# football_robot_main_board.net
KiCad netlist of a schematic drawn in Altium Designer
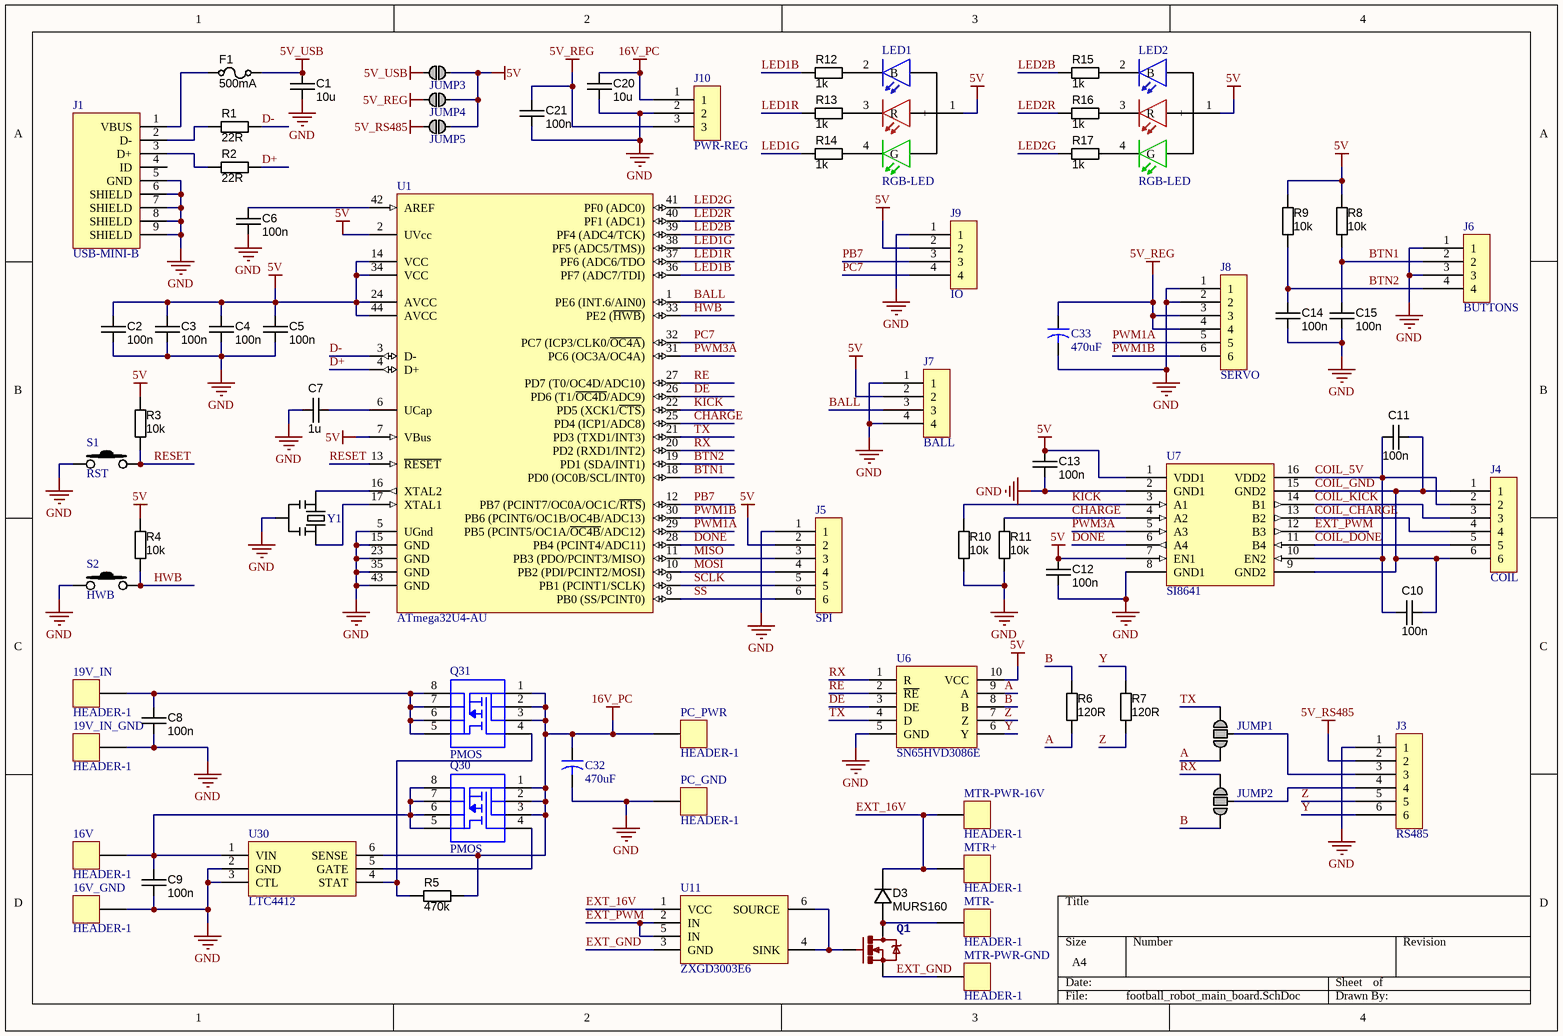
[diagram p0: football_robot_main_board.SchDoc]

(export (version "E")
  (design (tool "Eeschema 10.0.6"))
  (components
    (comp (ref "16V")
      (value "HEADER-1")
      (footprint "POWER-VIA")
      (libsource (lib "connectors") (part "HEADER-1"))
    )
    (comp (ref "16V_GND")
      (value "HEADER-1")
      (footprint "POWER-VIA")
      (libsource (lib "connectors") (part "HEADER-1"))
    )
    (comp (ref "19V_IN")
      (value "HEADER-1")
      (footprint "POWER-VIA")
      (libsource (lib "connectors") (part "HEADER-1"))
    )
    (comp (ref "19V_IN_GND")
      (value "HEADER-1")
      (footprint "POWER-VIA")
      (libsource (lib "connectors") (part "HEADER-1"))
    )
    (comp (ref "C1")
      (value "10u")
      (footprint "CAPC3216X180N")
      (description "Capacitor SMD Cer 10uF 10% 10V X5R 1206")
      (fields (field (name "TOLERANCE") "±10%"))
      (libsource (lib "PBL - Capacitors") (part "CAPC_10u_1206_10V"))
    )
    (comp (ref "C2")
      (value "100n")
      (footprint "CAPC1608X90N")
      (description "Capacitor SMD Cer 10nF 10% 50V X7R 0603")
      (fields (field (name "TOLERANCE") "±10%"))
      (libsource (lib "PBL - Capacitors") (part "CAPC_10n_0603_X7R_50V_10%"))
    )
    (comp (ref "C3")
      (value "100n")
      (footprint "CAPC1608X90N")
      (description "Capacitor SMD Cer 10nF 10% 50V X7R 0603")
      (fields (field (name "TOLERANCE") "±10%"))
      (libsource (lib "PBL - Capacitors") (part "CAPC_10n_0603_X7R_50V_10%"))
    )
    (comp (ref "C4")
      (value "100n")
      (footprint "CAPC1608X90N")
      (description "Capacitor SMD Cer 10nF 10% 50V X7R 0603")
      (fields (field (name "TOLERANCE") "±10%"))
      (libsource (lib "PBL - Capacitors") (part "CAPC_10n_0603_X7R_50V_10%"))
    )
    (comp (ref "C5")
      (value "100n")
      (footprint "CAPC1608X90N")
      (description "Capacitor SMD Cer 10nF 10% 50V X7R 0603")
      (fields (field (name "TOLERANCE") "±10%"))
      (libsource (lib "PBL - Capacitors") (part "CAPC_10n_0603_X7R_50V_10%"))
    )
    (comp (ref "C6")
      (value "100n")
      (footprint "CAPC1608X90N")
      (description "Capacitor SMD Cer 10nF 10% 50V X7R 0603")
      (fields (field (name "TOLERANCE") "±10%"))
      (libsource (lib "PBL - Capacitors") (part "CAPC_10n_0603_X7R_50V_10%"))
    )
    (comp (ref "C7")
      (value "1u")
      (footprint "CAPC1608X90N")
      (description "Capacitor SMD Cer 10nF 10% 50V X7R 0603")
      (fields (field (name "TOLERANCE") "±10%"))
      (libsource (lib "PBL - Capacitors") (part "CAPC_10n_0603_X7R_50V_10%"))
    )
    (comp (ref "C8")
      (value "100n")
      (footprint "CAPC1608X90N")
      (description "Capacitor SMD Cer 10nF 10% 50V X7R 0603")
      (fields (field (name "TOLERANCE") "±10%"))
      (libsource (lib "PBL - Capacitors") (part "CAPC_10n_0603_X7R_50V_10%"))
    )
    (comp (ref "C9")
      (value "100n")
      (footprint "CAPC1608X90N")
      (description "Capacitor SMD Cer 10nF 10% 50V X7R 0603")
      (fields (field (name "TOLERANCE") "±10%"))
      (libsource (lib "PBL - Capacitors") (part "CAPC_10n_0603_X7R_50V_10%"))
    )
    (comp (ref "C10")
      (value "100n")
      (footprint "CAPC1608X90N")
      (description "Capacitor SMD Cer 10nF 10% 50V X7R 0603")
      (fields (field (name "TOLERANCE") "±10%"))
      (libsource (lib "PBL - Capacitors") (part "CAPC_10n_0603_X7R_50V_10%"))
    )
    (comp (ref "C11")
      (value "100n")
      (footprint "CAPC1608X90N")
      (description "Capacitor SMD Cer 10nF 10% 50V X7R 0603")
      (fields (field (name "TOLERANCE") "±10%"))
      (libsource (lib "PBL - Capacitors") (part "CAPC_10n_0603_X7R_50V_10%"))
    )
    (comp (ref "C12")
      (value "100n")
      (footprint "CAPC1608X90N")
      (description "Capacitor SMD Cer 10nF 10% 50V X7R 0603")
      (fields (field (name "TOLERANCE") "±10%"))
      (libsource (lib "PBL - Capacitors") (part "CAPC_10n_0603_X7R_50V_10%"))
    )
    (comp (ref "C13")
      (value "100n")
      (footprint "CAPC1608X90N")
      (description "Capacitor SMD Cer 10nF 10% 50V X7R 0603")
      (fields (field (name "TOLERANCE") "±10%"))
      (libsource (lib "PBL - Capacitors") (part "CAPC_10n_0603_X7R_50V_10%"))
    )
    (comp (ref "C14")
      (value "100n")
      (footprint "CAPC1608X90N")
      (description "Capacitor SMD Cer 10nF 10% 50V X7R 0603")
      (fields (field (name "TOLERANCE") "±10%"))
      (libsource (lib "PBL - Capacitors") (part "CAPC_10n_0603_X7R_50V_10%"))
    )
    (comp (ref "C15")
      (value "100n")
      (footprint "CAPC1608X90N")
      (description "Capacitor SMD Cer 10nF 10% 50V X7R 0603")
      (fields (field (name "TOLERANCE") "±10%"))
      (libsource (lib "PBL - Capacitors") (part "CAPC_10n_0603_X7R_50V_10%"))
    )
    (comp (ref "C20")
      (value "10u")
      (footprint "CAPC3216X180N")
      (description "Capacitor SMD Cer 10uF 10% 10V X5R 1206")
      (fields (field (name "TOLERANCE") "±10%"))
      (libsource (lib "PBL - Capacitors") (part "CAPC_10u_1206_10V"))
    )
    (comp (ref "C21")
      (value "100n")
      (footprint "CAPC1608X90N")
      (description "Capacitor SMD Cer 10nF 10% 50V X7R 0603")
      (fields (field (name "TOLERANCE") "±10%"))
      (libsource (lib "PBL - Capacitors") (part "CAPC_10n_0603_X7R_50V_10%"))
    )
    (comp (ref "C32")
      (value "470uF")
      (footprint "CAPR5-4X5")
      (description "Capacitor")
      (fields (field (name "PUBLISHER") "Altium Limited"))
      (libsource (lib "Miscellaneous Devices") (part "Cap2"))
    )
    (comp (ref "C33")
      (value "470uF")
      (footprint "CAPR5-4X5")
      (description "Capacitor")
      (fields (field (name "PUBLISHER") "Altium Limited"))
      (libsource (lib "Miscellaneous Devices") (part "Cap2"))
    )
    (comp (ref "D3")
      (value "MURS160")
      (footprint "DO-214AA")
      (description "Diode SMD 100V 1.5A SMA")
      (libsource (lib "PBL - Diodes") (part "DIODE_100V_1.5A_SMA"))
    )
    (comp (ref "F1")
      (value "500mA")
      (footprint "RESC3216X70N")
      (description "Fuse 160mA 63VDC 1206 SMD")
      (libsource (lib "PBL - Fuses and Protection") (part "FUSE_160mA_1206"))
    )
    (comp (ref "J1")
      (value "USB-MINI-B")
      (footprint "USB-B-MINI")
      (libsource (lib "connectors") (part "USB-B-MINI"))
    )
    (comp (ref "J3")
      (value "RS485")
      (footprint "MICRO-MATCH-6")
      (libsource (lib "connectors") (part "HEADER-6"))
    )
    (comp (ref "J4")
      (value "COIL")
      (footprint "MICRO-MATCH-6")
      (libsource (lib "connectors") (part "HEADER-6"))
    )
    (comp (ref "J5")
      (value "SPI")
      (footprint "MICRO-MATCH-6")
      (libsource (lib "connectors") (part "HEADER-6"))
    )
    (comp (ref "J6")
      (value "BUTTONS")
      (footprint "MICRO-MATCH-4")
      (libsource (lib "connectors") (part "HEADER-4"))
    )
    (comp (ref "J7")
      (value "BALL")
      (footprint "MICRO-MATCH-4")
      (libsource (lib "connectors") (part "HEADER-4"))
    )
    (comp (ref "J8")
      (value "SERVO")
      (footprint "MICRO-MATCH-6")
      (libsource (lib "connectors") (part "HEADER-6"))
    )
    (comp (ref "J9")
      (value "IO")
      (footprint "MICRO-MATCH-4")
      (libsource (lib "connectors") (part "HEADER-4"))
    )
    (comp (ref "J10")
      (value "PWR-REG")
      (footprint "PIN-HEADER-3")
      (libsource (lib "connectors") (part "HEADER-3"))
    )
    (comp (ref "JUMP1")
      (value "JUMPER")
      (footprint "JUMPER-SMD-3WAY")
      (libsource (lib "connectors") (part "JUMPER-SMD-3WAY"))
    )
    (comp (ref "JUMP2")
      (value "JUMPER")
      (footprint "JUMPER-SMD-3WAY")
      (libsource (lib "connectors") (part "JUMPER-SMD-3WAY"))
    )
    (comp (ref "JUMP3")
      (value "JUMPER")
      (footprint "JUMPER-SMD-1010")
      (libsource (lib "connectors") (part "JUMPER-SMD"))
    )
    (comp (ref "JUMP4")
      (value "JUMPER")
      (footprint "JUMPER-SMD-1010")
      (libsource (lib "connectors") (part "JUMPER-SMD"))
    )
    (comp (ref "JUMP5")
      (value "JUMPER")
      (footprint "JUMPER-SMD-1010")
      (libsource (lib "connectors") (part "JUMPER-SMD"))
    )
    (comp (ref "LED1") (value "RGB-LED") (footprint "RGB-LED") (libsource (lib "misc") (part "RGB-LED")))
    (comp (ref "LED2") (value "RGB-LED") (footprint "RGB-LED") (libsource (lib "misc") (part "RGB-LED")))
    (comp (ref "MTR+") (value "HEADER-1") (footprint "POWER-VIA") (libsource (lib "") (part "HEADER-1_1")))
    (comp (ref "MTR-") (value "HEADER-1") (footprint "POWER-VIA") (libsource (lib "") (part "HEADER-1_1")))
    (comp (ref "MTR-PWR-16V")
      (value "HEADER-1")
      (footprint "POWER-VIA")
      (libsource (lib "") (part "HEADER-1_1"))
    )
    (comp (ref "MTR-PWR-GND")
      (value "HEADER-1")
      (footprint "POWER-VIA")
      (libsource (lib "") (part "HEADER-1_1"))
    )
    (comp (ref "PC_GND") (value "HEADER-1") (footprint "POWER-VIA") (libsource (lib "") (part "HEADER-1_1")))
    (comp (ref "PC_PWR") (value "HEADER-1") (footprint "POWER-VIA") (libsource (lib "") (part "HEADER-1_1")))
    (comp (ref "Q1") (value "MOSFET-N") (footprint "SOT669") (libsource (lib "mosfets") (part "MOSFET-N")))
    (comp (ref "Q30") (value "PMOS") (footprint "SO8") (libsource (lib "misc") (part "PMOS")))
    (comp (ref "Q31") (value "PMOS") (footprint "SO8") (libsource (lib "misc") (part "PMOS")))
    (comp (ref "R1")
      (value "22R")
      (footprint "RESC1608N_ZERO")
      (description "Resistor SMD chip 0.0 Ohm 0.1W 0603")
      (fields (field (name "TOLERANCE") "±5%"))
      (libsource (lib "") (part "RES_0R_0603_2"))
    )
    (comp (ref "R2")
      (value "22R")
      (footprint "RESC1608N_ZERO")
      (description "Resistor SMD chip 0.0 Ohm 0.1W 0603")
      (fields (field (name "TOLERANCE") "±5%"))
      (libsource (lib "") (part "RES_0R_0603_2"))
    )
    (comp (ref "R3")
      (value "10k")
      (footprint "RESC1608N_ZERO")
      (description "Resistor SMD chip 0.0 Ohm 0.1W 0603")
      (fields (field (name "TOLERANCE") "±5%"))
      (libsource (lib "") (part "RES_0R_0603_1"))
    )
    (comp (ref "R4")
      (value "10k")
      (footprint "RESC1608N_ZERO")
      (description "Resistor SMD chip 0.0 Ohm 0.1W 0603")
      (fields (field (name "TOLERANCE") "±5%"))
      (libsource (lib "") (part "RES_0R_0603_1"))
    )
    (comp (ref "R5")
      (value "470k")
      (footprint "RESC1608N_ZERO")
      (description "Resistor SMD chip 0.0 Ohm 0.1W 0603")
      (fields (field (name "TOLERANCE") "±5%"))
      (libsource (lib "PBL - Resistors") (part "RES_0R_0603"))
    )
    (comp (ref "R6")
      (value "120R")
      (footprint "RESC1608N_ZERO")
      (description "Resistor SMD chip 0.0 Ohm 0.1W 0603")
      (fields (field (name "TOLERANCE") "±5%"))
      (libsource (lib "") (part "RES_0R_0603_1"))
    )
    (comp (ref "R7")
      (value "120R")
      (footprint "RESC1608N_ZERO")
      (description "Resistor SMD chip 0.0 Ohm 0.1W 0603")
      (fields (field (name "TOLERANCE") "±5%"))
      (libsource (lib "") (part "RES_0R_0603_1"))
    )
    (comp (ref "R8")
      (value "10k")
      (footprint "RESC1608N_ZERO")
      (description "Resistor SMD chip 0.0 Ohm 0.1W 0603")
      (fields (field (name "TOLERANCE") "±5%"))
      (libsource (lib "") (part "RES_0R_0603_1"))
    )
    (comp (ref "R9")
      (value "10k")
      (footprint "RESC1608N_ZERO")
      (description "Resistor SMD chip 0.0 Ohm 0.1W 0603")
      (fields (field (name "TOLERANCE") "±5%"))
      (libsource (lib "") (part "RES_0R_0603_1"))
    )
    (comp (ref "R10")
      (value "10k")
      (footprint "RESC1608N_ZERO")
      (description "Resistor SMD chip 0.0 Ohm 0.1W 0603")
      (fields (field (name "TOLERANCE") "±5%"))
      (libsource (lib "") (part "RES_0R_0603_1"))
    )
    (comp (ref "R11")
      (value "10k")
      (footprint "RESC1608N_ZERO")
      (description "Resistor SMD chip 0.0 Ohm 0.1W 0603")
      (fields (field (name "TOLERANCE") "±5%"))
      (libsource (lib "") (part "RES_0R_0603_1"))
    )
    (comp (ref "R12")
      (value "1k")
      (footprint "RESC1608N_ZERO")
      (description "Resistor SMD chip 0.0 Ohm 0.1W 0603")
      (fields (field (name "TOLERANCE") "±5%"))
      (libsource (lib "PBL - Resistors") (part "RES_0R_0603"))
    )
    (comp (ref "R13")
      (value "1k")
      (footprint "RESC1608N_ZERO")
      (description "Resistor SMD chip 0.0 Ohm 0.1W 0603")
      (fields (field (name "TOLERANCE") "±5%"))
      (libsource (lib "PBL - Resistors") (part "RES_0R_0603"))
    )
    (comp (ref "R14")
      (value "1k")
      (footprint "RESC1608N_ZERO")
      (description "Resistor SMD chip 0.0 Ohm 0.1W 0603")
      (fields (field (name "TOLERANCE") "±5%"))
      (libsource (lib "PBL - Resistors") (part "RES_0R_0603"))
    )
    (comp (ref "R15")
      (value "1k")
      (footprint "RESC1608N_ZERO")
      (description "Resistor SMD chip 0.0 Ohm 0.1W 0603")
      (fields (field (name "TOLERANCE") "±5%"))
      (libsource (lib "PBL - Resistors") (part "RES_0R_0603"))
    )
    (comp (ref "R16")
      (value "1k")
      (footprint "RESC1608N_ZERO")
      (description "Resistor SMD chip 0.0 Ohm 0.1W 0603")
      (fields (field (name "TOLERANCE") "±5%"))
      (libsource (lib "PBL - Resistors") (part "RES_0R_0603"))
    )
    (comp (ref "R17")
      (value "1k")
      (footprint "RESC1608N_ZERO")
      (description "Resistor SMD chip 0.0 Ohm 0.1W 0603")
      (fields (field (name "TOLERANCE") "±5%"))
      (libsource (lib "PBL - Resistors") (part "RES_0R_0603"))
    )
    (comp (ref "S1") (value "RST") (footprint "DTSM-32S-B") (libsource (lib "switches") (part "SW-PB-OPEN")))
    (comp (ref "S2") (value "HWB") (footprint "DTSM-32S-B") (libsource (lib "switches") (part "SW-PB-OPEN")))
    (comp (ref "U1")
      (value "ATmega32U4-AU")
      (footprint "44ML_N")
      (fields (field (name "PUBLISHER") "Altium Limited"))
      (libsource (lib "Atmel Microcontroller 8-Bit megaAVR") (part "ATmega32U4-AU"))
    )
    (comp (ref "U6")
      (value "SN65HVD3086E")
      (footprint "SOP10")
      (libsource (lib "texas_instruments") (part "SN65HVD3086E"))
    )
    (comp (ref "U7") (value "SI8641") (footprint "SOIC16") (libsource (lib "digital") (part "SI8641")))
    (comp (ref "U11")
      (value "ZXGD3003E6")
      (footprint "SOT23-6-EEPROM")
      (description "MOSFET driver")
      (libsource (lib "misc") (part "ZXGD3003E6"))
    )
    (comp (ref "U30") (value "LTC4412") (footprint "TSOT-23-6") (libsource (lib "digital") (part "LTC4412")))
    (comp (ref "Y1")
      (value "Resonator")
      (footprint "PBRC16.00MR")
      (libsource (lib "misc") (part "PBRC16.00MR"))
    )
  )
  (nets
    (net (code "1") (name "/A") (class "Default")
      (node (ref "JUMP1") (pin "3") (pinfunction "3_3") (pintype "passive"))
      (node (ref "R6") (pin "1") (pinfunction "1_1") (pintype "passive"))
      (node (ref "U6") (pin "9") (pinfunction "A_9") (pintype "passive"))
    )
    (net (code "2") (name "/B") (class "Default")
      (node (ref "JUMP2") (pin "3") (pinfunction "3_3") (pintype "passive"))
      (node (ref "R6") (pin "2") (pinfunction "2_2") (pintype "passive"))
      (node (ref "U6") (pin "8") (pinfunction "B_8") (pintype "passive"))
    )
    (net (code "3") (name "/BALL") (class "Default")
      (node (ref "J7") (pin "3") (pinfunction "3_3") (pintype "passive"))
      (node (ref "U1") (pin "1") (pinfunction "PE6_(INT.6/AIN0)_1") (pintype "bidirectional"))
    )
    (net (code "4") (name "/BTN1") (class "Default")
      (node (ref "C15") (pin "1") (pintype "passive"))
      (node (ref "J6") (pin "2") (pinfunction "2_2") (pintype "passive"))
      (node (ref "R8") (pin "1") (pinfunction "1_1") (pintype "passive"))
      (node (ref "U1") (pin "18") (pinfunction "PD0_(OC0B/SCL/INT0)_18") (pintype "bidirectional"))
    )
    (net (code "5") (name "/BTN2") (class "Default")
      (node (ref "C14") (pin "1") (pintype "passive"))
      (node (ref "J6") (pin "4") (pinfunction "4_4") (pintype "passive"))
      (node (ref "R9") (pin "1") (pinfunction "1_1") (pintype "passive"))
      (node (ref "U1") (pin "19") (pinfunction "PD1_(SDA/INT1)_19") (pintype "bidirectional"))
    )
    (net (code "6") (name "/CHARGE") (class "Default")
      (node (ref "R11") (pin "2") (pinfunction "2_2") (pintype "passive"))
      (node (ref "U1") (pin "25") (pinfunction "PD4_(ICP1/ADC8)_25") (pintype "bidirectional"))
      (node (ref "U7") (pin "4") (pinfunction "A2_4") (pintype "input"))
    )
    (net (code "7") (name "/COIL_5V") (class "Default")
      (node (ref "C10") (pin "1") (pintype "passive"))
      (node (ref "C11") (pin "1") (pintype "passive"))
      (node (ref "J4") (pin "2") (pinfunction "2_2") (pintype "passive"))
      (node (ref "U7") (pin "10") (pinfunction "EN2_10") (pintype "input"))
      (node (ref "U7") (pin "16") (pinfunction "VDD2_16") (pintype "power_in"))
    )
    (net (code "8") (name "/COIL_CHARGE") (class "Default")
      (node (ref "J4") (pin "4") (pinfunction "4_4") (pintype "passive"))
      (node (ref "U7") (pin "13") (pinfunction "B2_13") (pintype "output"))
    )
    (net (code "9") (name "/COIL_DONE") (class "Default")
      (node (ref "J4") (pin "5") (pinfunction "5_5") (pintype "passive"))
      (node (ref "U7") (pin "11") (pinfunction "B4_11") (pintype "input"))
    )
    (net (code "10") (name "/COIL_GND") (class "Default")
      (node (ref "C10") (pin "2") (pintype "passive"))
      (node (ref "C11") (pin "2") (pintype "passive"))
      (node (ref "J4") (pin "1") (pinfunction "1_1") (pintype "passive"))
      (node (ref "J4") (pin "6") (pinfunction "6_6") (pintype "passive"))
      (node (ref "U7") (pin "15") (pinfunction "GND2_15") (pintype "power_in"))
      (node (ref "U7") (pin "9") (pinfunction "GND2_9") (pintype "power_in"))
    )
    (net (code "11") (name "/COIL_KICK") (class "Default")
      (node (ref "J4") (pin "3") (pinfunction "3_3") (pintype "passive"))
      (node (ref "U7") (pin "14") (pinfunction "B1_14") (pintype "output"))
    )
    (net (code "12") (name "/D+") (class "Default")
      (node (ref "R2") (pin "2") (pinfunction "2_2") (pintype "passive"))
      (node (ref "U1") (pin "4") (pinfunction "D+_4") (pintype "bidirectional"))
    )
    (net (code "13") (name "/D-") (class "Default")
      (node (ref "R1") (pin "2") (pinfunction "2_2") (pintype "passive"))
      (node (ref "U1") (pin "3") (pinfunction "D-_3") (pintype "bidirectional"))
    )
    (net (code "14") (name "/DE") (class "Default")
      (node (ref "U1") (pin "26") (pinfunction "PD6_(T1/~{OC4D}/ADC9)_26") (pintype "bidirectional"))
      (node (ref "U6") (pin "3") (pinfunction "DE_3") (pintype "passive"))
    )
    (net (code "15") (name "/DONE") (class "Default")
      (node (ref "U1") (pin "28") (pinfunction "PB4_(PCINT4/ADC11)_28") (pintype "bidirectional"))
      (node (ref "U7") (pin "6") (pinfunction "A4_6") (pintype "output"))
    )
    (net (code "16") (name "/EXT_16V") (class "Default")
      (node (ref "D3") (pin "K") (pinfunction "K_K") (pintype "passive"))
      (node (ref "MTR+") (pin "1") (pinfunction "1_1") (pintype "passive"))
      (node (ref "MTR-PWR-16V") (pin "1") (pinfunction "1_1") (pintype "passive"))
      (node (ref "U11") (pin "1") (pinfunction "VCC_1") (pintype "passive"))
    )
    (net (code "17") (name "/EXT_GND") (class "Default")
      (node (ref "MTR-PWR-GND") (pin "1") (pinfunction "1_1") (pintype "passive"))
      (node (ref "Q1") (pin "S") (pinfunction "S_S") (pintype "passive"))
      (node (ref "U11") (pin "3") (pinfunction "GND_3") (pintype "passive"))
    )
    (net (code "18") (name "/EXT_PWM") (class "Default")
      (node (ref "U11") (pin "2") (pinfunction "IN_2") (pintype "passive"))
      (node (ref "U11") (pin "5") (pinfunction "IN_5") (pintype "passive"))
      (node (ref "U7") (pin "12") (pinfunction "B3_12") (pintype "output"))
    )
    (net (code "19") (name "/HWB") (class "Default")
      (node (ref "R4") (pin "1") (pinfunction "1_1") (pintype "passive"))
      (node (ref "S2") (pin "2") (pinfunction "2_2") (pintype "passive"))
      (node (ref "U1") (pin "33") (pinfunction "PE2_(~{HWB})_33") (pintype "bidirectional"))
    )
    (net (code "20") (name "/KICK") (class "Default")
      (node (ref "R10") (pin "2") (pinfunction "2_2") (pintype "passive"))
      (node (ref "U1") (pin "22") (pinfunction "PD5_(XCK1/~{CTS})_22") (pintype "bidirectional"))
      (node (ref "U7") (pin "3") (pinfunction "A1_3") (pintype "input"))
    )
    (net (code "21") (name "/LED1B") (class "Default")
      (node (ref "R12") (pin "2") (pinfunction "2_2") (pintype "passive"))
      (node (ref "U1") (pin "36") (pinfunction "PF7_(ADC7/TDI)_36") (pintype "bidirectional"))
    )
    (net (code "22") (name "/LED1G") (class "Default")
      (node (ref "R14") (pin "2") (pinfunction "2_2") (pintype "passive"))
      (node (ref "U1") (pin "38") (pinfunction "PF5_(ADC5/TMS))_38") (pintype "bidirectional"))
    )
    (net (code "23") (name "/LED1R") (class "Default")
      (node (ref "R13") (pin "2") (pinfunction "2_2") (pintype "passive"))
      (node (ref "U1") (pin "37") (pinfunction "PF6_(ADC6/TDO_37") (pintype "bidirectional"))
    )
    (net (code "24") (name "/LED2B") (class "Default")
      (node (ref "R15") (pin "2") (pinfunction "2_2") (pintype "passive"))
      (node (ref "U1") (pin "39") (pinfunction "PF4_(ADC4/TCK)_39") (pintype "bidirectional"))
    )
    (net (code "25") (name "/LED2G") (class "Default")
      (node (ref "R17") (pin "2") (pinfunction "2_2") (pintype "passive"))
      (node (ref "U1") (pin "41") (pinfunction "PF0_(ADC0)_41") (pintype "bidirectional"))
    )
    (net (code "26") (name "/LED2R") (class "Default")
      (node (ref "R16") (pin "2") (pinfunction "2_2") (pintype "passive"))
      (node (ref "U1") (pin "40") (pinfunction "PF1_(ADC1)_40") (pintype "bidirectional"))
    )
    (net (code "27") (name "/MISO") (class "Default")
      (node (ref "J5") (pin "3") (pinfunction "3_3") (pintype "passive"))
      (node (ref "U1") (pin "11") (pinfunction "PB3_(PDO/PCINT3/MISO)_11") (pintype "bidirectional"))
    )
    (net (code "28") (name "/MOSI") (class "Default")
      (node (ref "J5") (pin "4") (pinfunction "4_4") (pintype "passive"))
      (node (ref "U1") (pin "10") (pinfunction "PB2_(PDI/PCINT2/MOSI)_10") (pintype "bidirectional"))
    )
    (net (code "29") (name "/PB7") (class "Default")
      (node (ref "J9") (pin "3") (pinfunction "3_3") (pintype "passive"))
      (node (ref "U1") (pin "12") (pinfunction "PB7_(PCINT7/OC0A/OC1C/~{RTS})_12") (pintype "bidirectional"))
    )
    (net (code "30") (name "/PC7") (class "Default")
      (node (ref "J9") (pin "4") (pinfunction "4_4") (pintype "passive"))
      (node (ref "U1") (pin "32") (pinfunction "PC7_(ICP3/CLK0/~{OC4A})_32") (pintype "bidirectional"))
    )
    (net (code "31") (name "/PWM1A") (class "Default")
      (node (ref "J8") (pin "5") (pinfunction "5_5") (pintype "passive"))
      (node (ref "U1") (pin "29") (pinfunction "PB5_(PCINT5/OC1A/~{OC4B}/ADC12)_29") (pintype "bidirectional"))
    )
    (net (code "32") (name "/PWM1B") (class "Default")
      (node (ref "J8") (pin "6") (pinfunction "6_6") (pintype "passive"))
      (node (ref "U1") (pin "30") (pinfunction "PB6_(PCINT6/OC1B/OC4B/ADC13)_30") (pintype "bidirectional"))
    )
    (net (code "33") (name "/PWM3A") (class "Default")
      (node (ref "U1") (pin "31") (pinfunction "PC6_(OC3A/OC4A)_31") (pintype "bidirectional"))
      (node (ref "U7") (pin "5") (pinfunction "A3_5") (pintype "input"))
    )
    (net (code "34") (name "/RE") (class "Default")
      (node (ref "U1") (pin "27") (pinfunction "PD7_(T0/OC4D/ADC10)_27") (pintype "bidirectional"))
      (node (ref "U6") (pin "2") (pinfunction "~{RE}_2") (pintype "passive"))
    )
    (net (code "35") (name "/RESET") (class "Default")
      (node (ref "R3") (pin "1") (pinfunction "1_1") (pintype "passive"))
      (node (ref "S1") (pin "2") (pinfunction "2_2") (pintype "passive"))
      (node (ref "U1") (pin "13") (pinfunction "~{RESET}_13") (pintype "input"))
    )
    (net (code "36") (name "/RX") (class "Default")
      (node (ref "JUMP2") (pin "1") (pinfunction "1_1") (pintype "passive"))
      (node (ref "U1") (pin "20") (pinfunction "PD2_(RXD1/INT2)_20") (pintype "bidirectional"))
      (node (ref "U6") (pin "1") (pinfunction "R_1") (pintype "passive"))
    )
    (net (code "37") (name "/SCLK") (class "Default")
      (node (ref "J5") (pin "5") (pinfunction "5_5") (pintype "passive"))
      (node (ref "U1") (pin "9") (pinfunction "PB1_(PCINT1/SCLK)_9") (pintype "bidirectional"))
    )
    (net (code "38") (name "/SS") (class "Default")
      (node (ref "J5") (pin "6") (pinfunction "6_6") (pintype "passive"))
      (node (ref "U1") (pin "8") (pinfunction "PB0_(SS/PCINT0)_8") (pintype "bidirectional"))
    )
    (net (code "39") (name "/TX") (class "Default")
      (node (ref "JUMP1") (pin "1") (pinfunction "1_1") (pintype "passive"))
      (node (ref "U1") (pin "21") (pinfunction "PD3_(TXD1/INT3)_21") (pintype "bidirectional"))
      (node (ref "U6") (pin "4") (pinfunction "D_4") (pintype "passive"))
    )
    (net (code "40") (name "/Y") (class "Default")
      (node (ref "J3") (pin "6") (pinfunction "6_6") (pintype "passive"))
      (node (ref "R7") (pin "2") (pinfunction "2_2") (pintype "passive"))
      (node (ref "U6") (pin "6") (pinfunction "Y_6") (pintype "passive"))
    )
    (net (code "41") (name "/Z") (class "Default")
      (node (ref "J3") (pin "5") (pinfunction "5_5") (pintype "passive"))
      (node (ref "R7") (pin "1") (pinfunction "1_1") (pintype "passive"))
      (node (ref "U6") (pin "7") (pinfunction "Z_7") (pintype "passive"))
    )
    (net (code "42") (name "5V") (class "Default")
      (node (ref "C12") (pin "2") (pintype "passive"))
      (node (ref "C13") (pin "1") (pintype "passive"))
      (node (ref "C2") (pin "2") (pintype "passive"))
      (node (ref "C3") (pin "1") (pintype "passive"))
      (node (ref "C4") (pin "1") (pintype "passive"))
      (node (ref "C5") (pin "2") (pintype "passive"))
      (node (ref "J5") (pin "2") (pinfunction "2_2") (pintype "passive"))
      (node (ref "J7") (pin "2") (pinfunction "2_2") (pintype "passive"))
      (node (ref "J9") (pin "2") (pinfunction "2_2") (pintype "passive"))
      (node (ref "JUMP3") (pin "2") (pinfunction "2_2") (pintype "passive"))
      (node (ref "JUMP4") (pin "2") (pinfunction "2_2") (pintype "passive"))
      (node (ref "JUMP5") (pin "2") (pinfunction "2_2") (pintype "passive"))
      (node (ref "LED1") (pin "1") (pinfunction "+_1") (pintype "passive"))
      (node (ref "LED2") (pin "1") (pinfunction "+_1") (pintype "passive"))
      (node (ref "R3") (pin "2") (pinfunction "2_2") (pintype "passive"))
      (node (ref "R4") (pin "2") (pinfunction "2_2") (pintype "passive"))
      (node (ref "R8") (pin "2") (pinfunction "2_2") (pintype "passive"))
      (node (ref "R9") (pin "2") (pinfunction "2_2") (pintype "passive"))
      (node (ref "U1") (pin "14") (pinfunction "VCC_14") (pintype "power_in"))
      (node (ref "U1") (pin "2") (pinfunction "UVcc_2") (pintype "power_in"))
      (node (ref "U1") (pin "24") (pinfunction "AVCC_24") (pintype "power_in"))
      (node (ref "U1") (pin "34") (pinfunction "VCC_34") (pintype "power_in"))
      (node (ref "U1") (pin "44") (pinfunction "AVCC_44") (pintype "power_in"))
      (node (ref "U1") (pin "7") (pinfunction "VBus_7") (pintype "input"))
      (node (ref "U6") (pin "10") (pinfunction "VCC_10") (pintype "passive"))
      (node (ref "U7") (pin "1") (pinfunction "VDD1_1") (pintype "power_in"))
      (node (ref "U7") (pin "7") (pinfunction "EN1_7") (pintype "input"))
    )
    (net (code "43") (name "5V_REG") (class "Default")
      (node (ref "C21") (pin "2") (pintype "passive"))
      (node (ref "C33") (pin "1") (pinfunction "1_1") (pintype "passive"))
      (node (ref "J10") (pin "3") (pinfunction "3_3") (pintype "passive"))
      (node (ref "J8") (pin "3") (pinfunction "3_3") (pintype "passive"))
      (node (ref "J8") (pin "4") (pinfunction "4_4") (pintype "passive"))
      (node (ref "JUMP4") (pin "1") (pinfunction "1_1") (pintype "passive"))
    )
    (net (code "44") (name "5V_RS485") (class "Default")
      (node (ref "J3") (pin "2") (pinfunction "2_2") (pintype "passive"))
      (node (ref "JUMP5") (pin "1") (pinfunction "1_1") (pintype "passive"))
    )
    (net (code "45") (name "5V_USB") (class "Default")
      (node (ref "C1") (pin "2") (pintype "passive"))
      (node (ref "F1") (pin "2") (pinfunction "2_2") (pintype "passive"))
      (node (ref "JUMP3") (pin "1") (pinfunction "1_1") (pintype "passive"))
    )
    (net (code "46") (name "16V_PC") (class "Default")
      (node (ref "C20") (pin "2") (pintype "passive"))
      (node (ref "C32") (pin "1") (pinfunction "1_1") (pintype "passive"))
      (node (ref "J10") (pin "1") (pinfunction "1_1") (pintype "passive"))
      (node (ref "PC_PWR") (pin "1") (pinfunction "1_1") (pintype "passive"))
      (node (ref "Q30") (pin "1") (pinfunction "1_1") (pintype "passive"))
      (node (ref "Q30") (pin "2") (pinfunction "2_2") (pintype "passive"))
      (node (ref "Q30") (pin "3") (pinfunction "3_3") (pintype "passive"))
      (node (ref "Q31") (pin "1") (pinfunction "1_1") (pintype "passive"))
      (node (ref "Q31") (pin "2") (pinfunction "2_2") (pintype "passive"))
      (node (ref "Q31") (pin "3") (pinfunction "3_3") (pintype "passive"))
      (node (ref "R5") (pin "1") (pinfunction "1_1") (pintype "passive"))
      (node (ref "U30") (pin "6") (pinfunction "SENSE_6") (pintype "passive"))
    )
    (net (code "47") (name "GND") (class "Default")
      (node (ref "16V_GND") (pin "1") (pinfunction "1_1") (pintype "passive"))
      (node (ref "19V_IN_GND") (pin "1") (pinfunction "1_1") (pintype "passive"))
      (node (ref "C1") (pin "1") (pintype "passive"))
      (node (ref "C12") (pin "1") (pintype "passive"))
      (node (ref "C13") (pin "2") (pintype "passive"))
      (node (ref "C14") (pin "2") (pintype "passive"))
      (node (ref "C15") (pin "2") (pintype "passive"))
      (node (ref "C2") (pin "1") (pintype "passive"))
      (node (ref "C20") (pin "1") (pintype "passive"))
      (node (ref "C21") (pin "1") (pintype "passive"))
      (node (ref "C3") (pin "2") (pintype "passive"))
      (node (ref "C32") (pin "2") (pinfunction "2_2") (pintype "passive"))
      (node (ref "C33") (pin "2") (pinfunction "2_2") (pintype "passive"))
      (node (ref "C4") (pin "2") (pintype "passive"))
      (node (ref "C5") (pin "1") (pintype "passive"))
      (node (ref "C6") (pin "1") (pintype "passive"))
      (node (ref "C7") (pin "1") (pintype "passive"))
      (node (ref "C8") (pin "2") (pintype "passive"))
      (node (ref "C9") (pin "2") (pintype "passive"))
      (node (ref "J1") (pin "5") (pinfunction "GND_5") (pintype "passive"))
      (node (ref "J1") (pin "6") (pinfunction "SHIELD_6") (pintype "passive"))
      (node (ref "J1") (pin "7") (pinfunction "SHIELD_7") (pintype "passive"))
      (node (ref "J1") (pin "8") (pinfunction "SHIELD_8") (pintype "passive"))
      (node (ref "J1") (pin "9") (pinfunction "SHIELD_9") (pintype "passive"))
      (node (ref "J10") (pin "2") (pinfunction "2_2") (pintype "passive"))
      (node (ref "J3") (pin "1") (pinfunction "1_1") (pintype "passive"))
      (node (ref "J5") (pin "1") (pinfunction "1_1") (pintype "passive"))
      (node (ref "J6") (pin "1") (pinfunction "1_1") (pintype "passive"))
      (node (ref "J6") (pin "3") (pinfunction "3_3") (pintype "passive"))
      (node (ref "J7") (pin "1") (pinfunction "1_1") (pintype "passive"))
      (node (ref "J7") (pin "4") (pinfunction "4_4") (pintype "passive"))
      (node (ref "J8") (pin "1") (pinfunction "1_1") (pintype "passive"))
      (node (ref "J8") (pin "2") (pinfunction "2_2") (pintype "passive"))
      (node (ref "J9") (pin "1") (pinfunction "1_1") (pintype "passive"))
      (node (ref "PC_GND") (pin "1") (pinfunction "1_1") (pintype "passive"))
      (node (ref "R10") (pin "1") (pinfunction "1_1") (pintype "passive"))
      (node (ref "R11") (pin "1") (pinfunction "1_1") (pintype "passive"))
      (node (ref "S1") (pin "1") (pinfunction "1_1") (pintype "passive"))
      (node (ref "S2") (pin "1") (pinfunction "1_1") (pintype "passive"))
      (node (ref "U1") (pin "15") (pinfunction "GND_15") (pintype "power_in"))
      (node (ref "U1") (pin "23") (pinfunction "GND_23") (pintype "power_in"))
      (node (ref "U1") (pin "35") (pinfunction "GND_35") (pintype "power_in"))
      (node (ref "U1") (pin "43") (pinfunction "GND_43") (pintype "power_in"))
      (node (ref "U1") (pin "5") (pinfunction "UGnd_5") (pintype "power_in"))
      (node (ref "U30") (pin "2") (pinfunction "GND_2") (pintype "passive"))
      (node (ref "U30") (pin "3") (pinfunction "CTL_3") (pintype "passive"))
      (node (ref "U6") (pin "5") (pinfunction "GND_5") (pintype "passive"))
      (node (ref "U7") (pin "2") (pinfunction "GND1_2") (pintype "power_in"))
      (node (ref "U7") (pin "8") (pinfunction "GND1_8") (pintype "power_in"))
      (node (ref "Y1") (pin "2") (pinfunction "2_2") (pintype "passive"))
    )
    (net (code "48") (name "Net-(19V_IN-Pad1)") (class "Default")
      (node (ref "19V_IN") (pin "1") (pinfunction "1_1") (pintype "passive"))
      (node (ref "C8") (pin "1") (pintype "passive"))
      (node (ref "Q31") (pin "5") (pinfunction "5_5") (pintype "passive"))
      (node (ref "Q31") (pin "6") (pinfunction "6_6") (pintype "passive"))
      (node (ref "Q31") (pin "7") (pinfunction "7_7") (pintype "passive"))
      (node (ref "Q31") (pin "8") (pinfunction "8_8") (pintype "passive"))
    )
    (net (code "49") (name "Net-(D3-PadA)") (class "Default")
      (node (ref "D3") (pin "A") (pinfunction "A_A") (pintype "passive"))
      (node (ref "MTR-") (pin "1") (pinfunction "1_1") (pintype "passive"))
      (node (ref "Q1") (pin "D") (pinfunction "D_D") (pintype "passive"))
    )
    (net (code "50") (name "Net-(J1-D+)") (class "Default")
      (node (ref "J1") (pin "3") (pinfunction "D+_3") (pintype "passive"))
      (node (ref "R2") (pin "1") (pinfunction "1_1") (pintype "passive"))
    )
    (net (code "51") (name "Net-(J1-D-)") (class "Default")
      (node (ref "J1") (pin "2") (pinfunction "D-_2") (pintype "passive"))
      (node (ref "R1") (pin "1") (pinfunction "1_1") (pintype "passive"))
    )
    (net (code "52") (name "Net-(J1-VBUS)") (class "Default")
      (node (ref "F1") (pin "1") (pinfunction "1_1") (pintype "passive"))
      (node (ref "J1") (pin "1") (pinfunction "VBUS_1") (pintype "passive"))
    )
    (net (code "53") (name "Net-(J3-Pad3)") (class "Default")
      (node (ref "J3") (pin "3") (pinfunction "3_3") (pintype "passive"))
      (node (ref "JUMP1") (pin "2") (pinfunction "2_2") (pintype "passive"))
    )
    (net (code "54") (name "Net-(J3-Pad4)") (class "Default")
      (node (ref "J3") (pin "4") (pinfunction "4_4") (pintype "passive"))
      (node (ref "JUMP2") (pin "2") (pinfunction "2_2") (pintype "passive"))
    )
    (net (code "55") (name "Net-(LED1-B)") (class "Default")
      (node (ref "LED1") (pin "2") (pinfunction "B_2") (pintype "passive"))
      (node (ref "R12") (pin "1") (pinfunction "1_1") (pintype "passive"))
    )
    (net (code "56") (name "Net-(LED1-G)") (class "Default")
      (node (ref "LED1") (pin "4") (pinfunction "G_4") (pintype "passive"))
      (node (ref "R14") (pin "1") (pinfunction "1_1") (pintype "passive"))
    )
    (net (code "57") (name "Net-(LED1-R)") (class "Default")
      (node (ref "LED1") (pin "3") (pinfunction "R_3") (pintype "passive"))
      (node (ref "R13") (pin "1") (pinfunction "1_1") (pintype "passive"))
    )
    (net (code "58") (name "Net-(LED2-B)") (class "Default")
      (node (ref "LED2") (pin "2") (pinfunction "B_2") (pintype "passive"))
      (node (ref "R15") (pin "1") (pinfunction "1_1") (pintype "passive"))
    )
    (net (code "59") (name "Net-(LED2-G)") (class "Default")
      (node (ref "LED2") (pin "4") (pinfunction "G_4") (pintype "passive"))
      (node (ref "R17") (pin "1") (pinfunction "1_1") (pintype "passive"))
    )
    (net (code "60") (name "Net-(LED2-R)") (class "Default")
      (node (ref "LED2") (pin "3") (pinfunction "R_3") (pintype "passive"))
      (node (ref "R16") (pin "1") (pinfunction "1_1") (pintype "passive"))
    )
    (net (code "61") (name "Net-(U1-AREF)") (class "Default")
      (node (ref "C6") (pin "2") (pintype "passive"))
      (node (ref "U1") (pin "42") (pinfunction "AREF_42") (pintype "input"))
    )
    (net (code "62") (name "Net-(U1-UCap)") (class "Default")
      (node (ref "C7") (pin "2") (pintype "passive"))
      (node (ref "U1") (pin "6") (pinfunction "UCap_6") (pintype "passive"))
    )
    (net (code "63") (name "Net-(U1-XTAL1)") (class "Default")
      (node (ref "U1") (pin "17") (pinfunction "XTAL1_17") (pintype "input"))
      (node (ref "Y1") (pin "3") (pinfunction "3_3") (pintype "passive"))
    )
    (net (code "64") (name "Net-(U1-XTAL2)") (class "Default")
      (node (ref "U1") (pin "16") (pinfunction "XTAL2_16") (pintype "output"))
      (node (ref "Y1") (pin "1") (pinfunction "1_1") (pintype "passive"))
    )
    (net (code "65") (name "Net-(U11-SINK)") (class "Default")
      (node (ref "Q1") (pin "G") (pinfunction "G_G") (pintype "passive"))
      (node (ref "U11") (pin "4") (pinfunction "SINK_4") (pintype "passive"))
      (node (ref "U11") (pin "6") (pinfunction "SOURCE_6") (pintype "passive"))
    )
    (net (code "66") (name "Net-(U30-GATE)") (class "Default")
      (node (ref "Q30") (pin "4") (pinfunction "4_4") (pintype "passive"))
      (node (ref "U30") (pin "5") (pinfunction "GATE_5") (pintype "passive"))
    )
    (net (code "67") (name "Net-(U30-STAT)") (class "Default")
      (node (ref "Q31") (pin "4") (pinfunction "4_4") (pintype "passive"))
      (node (ref "R5") (pin "2") (pinfunction "2_2") (pintype "passive"))
      (node (ref "U30") (pin "4") (pinfunction "STAT_4") (pintype "passive"))
    )
    (net (code "68") (name "Net-(U30-VIN)") (class "Default")
      (node (ref "16V") (pin "1") (pinfunction "1_1") (pintype "passive"))
      (node (ref "C9") (pin "1") (pintype "passive"))
      (node (ref "Q30") (pin "5") (pinfunction "5_5") (pintype "passive"))
      (node (ref "Q30") (pin "6") (pinfunction "6_6") (pintype "passive"))
      (node (ref "Q30") (pin "7") (pinfunction "7_7") (pintype "passive"))
      (node (ref "Q30") (pin "8") (pinfunction "8_8") (pintype "passive"))
      (node (ref "U30") (pin "1") (pinfunction "VIN_1") (pintype "passive"))
    )
    (net (code "69") (name "unconnected-(J1-ID-Pad4)") (class "Default")
      (node (ref "J1") (pin "4") (pinfunction "ID_4") (pintype "passive"))
    )
  )
)
